# Sheet_1.net
KiCad netlist of a schematic drawn in Altium Designer
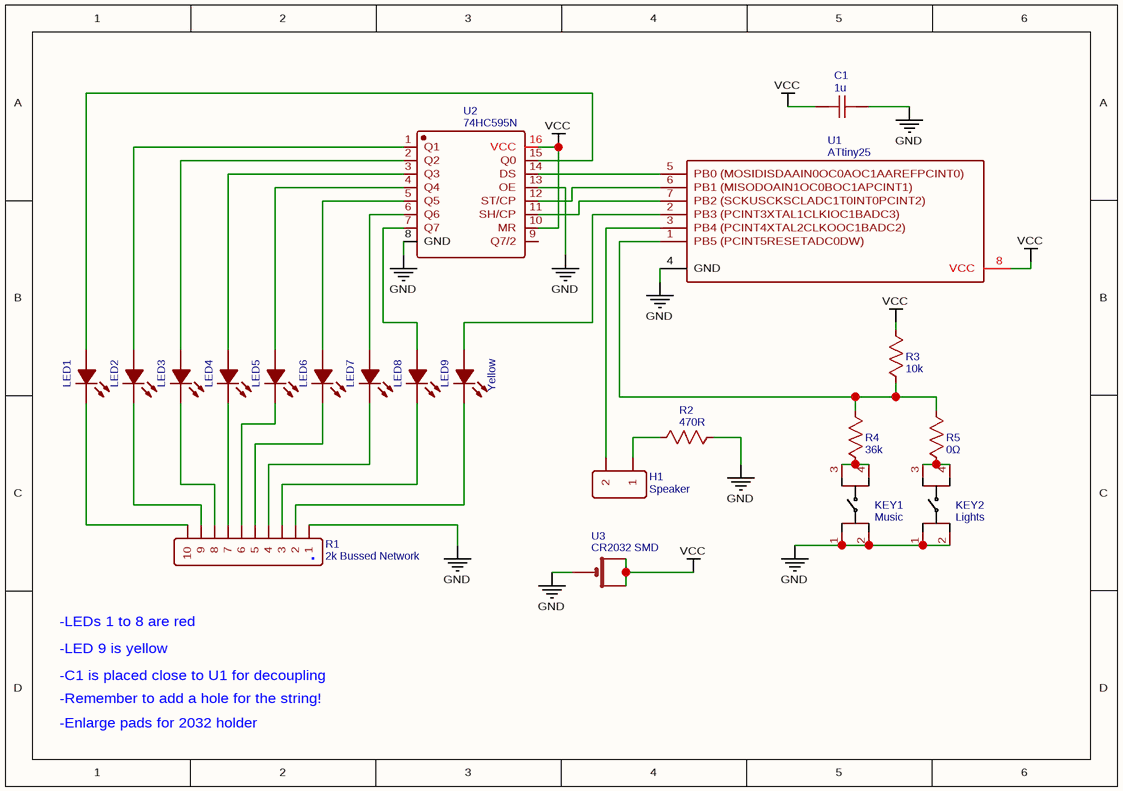
[diagram p0: Sheet_1.schdoc]

(export (version "E")
  (design (tool "Eeschema 10.0.6"))
  (components
    (comp (ref "C1") (value "1u") (libsource (lib "altium-import") (part "root_1_1u_")))
    (comp (ref "H1")
      (value "Speaker")
      (fields (field (name "BOM_MANUFACTURER PART") "826629-2") (field (name "BOM_SUPPLIER PART") "C86471"))
      (libsource (lib "altium-import") (part "root_3_Speaker_"))
    )
    (comp (ref "KEY1")
      (value "Music")
      (fields
        (field (name "BOM_MANUFACTURER PART") "TS-1102-5016")
        (field (name "BOM_SUPPLIER PART") "C111609")
        (field (name "CONTRIBUTOR") "EasyEDA")
      )
      (libsource (lib "altium-import") (part "root_1_Music_"))
    )
    (comp (ref "KEY2")
      (value "Lights")
      (fields
        (field (name "BOM_MANUFACTURER PART") "TS-1102-5016")
        (field (name "BOM_SUPPLIER PART") "C111609")
        (field (name "CONTRIBUTOR") "EasyEDA")
      )
      (libsource (lib "altium-import") (part "root_1_Lights_"))
    )
    (comp (ref "LED1")
      (value "204-10SURD/S530-A3")
      (fields (field (name "BOM_SUPPLIER PART") "C99772"))
      (libsource (lib "altium-import") (part "root_3_204-10SURD/S530-A3_"))
    )
    (comp (ref "LED2")
      (value "204-10SURD/S530-A3")
      (fields (field (name "BOM_SUPPLIER PART") "C99772"))
      (libsource (lib "altium-import") (part "root_3_204-10SURD/S530-A3_"))
    )
    (comp (ref "LED3")
      (value "204-10SURD/S530-A3")
      (fields (field (name "BOM_SUPPLIER PART") "C99772"))
      (libsource (lib "altium-import") (part "root_3_204-10SURD/S530-A3_"))
    )
    (comp (ref "LED4")
      (value "204-10SURD/S530-A3")
      (fields (field (name "BOM_SUPPLIER PART") "C99772"))
      (libsource (lib "altium-import") (part "root_3_204-10SURD/S530-A3_"))
    )
    (comp (ref "LED5")
      (value "204-10SURD/S530-A3")
      (fields (field (name "BOM_SUPPLIER PART") "C99772"))
      (libsource (lib "altium-import") (part "root_3_204-10SURD/S530-A3_"))
    )
    (comp (ref "LED6")
      (value "204-10SURD/S530-A3")
      (fields (field (name "BOM_SUPPLIER PART") "C99772"))
      (libsource (lib "altium-import") (part "root_3_204-10SURD/S530-A3_"))
    )
    (comp (ref "LED7")
      (value "204-10SURD/S530-A3")
      (fields (field (name "BOM_SUPPLIER PART") "C99772"))
      (libsource (lib "altium-import") (part "root_3_204-10SURD/S530-A3_"))
    )
    (comp (ref "LED8")
      (value "204-10SURD/S530-A3")
      (fields (field (name "BOM_SUPPLIER PART") "C99772"))
      (libsource (lib "altium-import") (part "root_3_204-10SURD/S530-A3_"))
    )
    (comp (ref "LED9")
      (value "Yellow")
      (fields
        (field (name "BOM_MANUFACTURER PART") "204-10SURD/S530-A3")
        (field (name "BOM_SUPPLIER PART") "C99772")
      )
      (libsource (lib "altium-import") (part "root_3_Yellow_"))
    )
    (comp (ref "R1")
      (value "2k Bussed Network")
      (fields
        (field (name "BOM_MANUFACTURER PART") "2.54mm 1*10P Straight Female header Gold-plated")
        (field (name "BOM_SUPPLIER PART") "C35445")
      )
      (libsource (lib "altium-import") (part "root_3_2k Bussed Network_"))
    )
    (comp (ref "R2") (value "470R") (libsource (lib "altium-import") (part "root_0_470R_")))
    (comp (ref "R3") (value "10k") (libsource (lib "altium-import") (part "root_1_10k_")))
    (comp (ref "R4") (value "36k") (libsource (lib "altium-import") (part "root_1_36k_")))
    (comp (ref "R5") (value "0Ω") (libsource (lib "altium-import") (part "root_1_0Ω_")))
    (comp (ref "U1") (value "ATtiny25") (libsource (lib "altium-import") (part "root_0_ATtiny25_")))
    (comp (ref "U2") (value "74HC595N") (libsource (lib "altium-import") (part "root_0_74HC595N_")))
    (comp (ref "U3")
      (value "CR2032 SMD")
      (fields (field (name "CONTRIBUTOR") "Adafruit"))
      (libsource (lib "altium-import") (part "root_0_CR2032 SMD_"))
    )
  )
  (nets
    (net (code "1") (name "GND") (class "Default")
      (node (ref "C1") (pin "1") (pinfunction "1_1") (pintype "passive"))
      (node (ref "KEY1") (pin "1") (pinfunction "1_1") (pintype "passive"))
      (node (ref "KEY1") (pin "2") (pinfunction "2_2") (pintype "passive"))
      (node (ref "KEY2") (pin "1") (pinfunction "1_1") (pintype "passive"))
      (node (ref "KEY2") (pin "2") (pinfunction "2_2") (pintype "passive"))
      (node (ref "R1") (pin "1") (pinfunction "1_1") (pintype "passive"))
      (node (ref "R2") (pin "2") (pinfunction "2_2") (pintype "passive"))
      (node (ref "U1") (pin "4") (pinfunction "GND_4") (pintype "passive"))
      (node (ref "U2") (pin "13") (pinfunction "OE_13") (pintype "passive"))
      (node (ref "U2") (pin "8") (pinfunction "GND_8") (pintype "passive"))
      (node (ref "U3") (pin "-") (pinfunction "-_-") (pintype "passive"))
    )
    (net (code "2") (name "Net-(H1-Pad1)") (class "Default")
      (node (ref "H1") (pin "1") (pinfunction "1_1") (pintype "passive"))
      (node (ref "R2") (pin "1") (pinfunction "1_1") (pintype "passive"))
    )
    (net (code "3") (name "Net-(KEY1-Pad3)") (class "Default")
      (node (ref "KEY1") (pin "3") (pinfunction "3_3") (pintype "passive"))
      (node (ref "KEY1") (pin "4") (pinfunction "4_4") (pintype "passive"))
      (node (ref "R4") (pin "1") (pinfunction "1_1") (pintype "passive"))
    )
    (net (code "4") (name "Net-(KEY2-Pad3)") (class "Default")
      (node (ref "KEY2") (pin "3") (pinfunction "3_3") (pintype "passive"))
      (node (ref "KEY2") (pin "4") (pinfunction "4_4") (pintype "passive"))
      (node (ref "R5") (pin "1") (pinfunction "1_1") (pintype "passive"))
    )
    (net (code "5") (name "Net-(LED1-A)") (class "Default")
      (node (ref "LED1") (pin "1") (pinfunction "A_1") (pintype "passive"))
      (node (ref "U2") (pin "15") (pinfunction "Q0_15") (pintype "passive"))
    )
    (net (code "6") (name "Net-(LED1-K)") (class "Default")
      (node (ref "LED1") (pin "2") (pinfunction "K_2") (pintype "passive"))
      (node (ref "R1") (pin "10") (pinfunction "10_10") (pintype "passive"))
    )
    (net (code "7") (name "Net-(LED2-A)") (class "Default")
      (node (ref "LED2") (pin "1") (pinfunction "A_1") (pintype "passive"))
      (node (ref "U2") (pin "1") (pinfunction "Q1_1") (pintype "passive"))
    )
    (net (code "8") (name "Net-(LED2-K)") (class "Default")
      (node (ref "LED2") (pin "2") (pinfunction "K_2") (pintype "passive"))
      (node (ref "R1") (pin "9") (pinfunction "9_9") (pintype "passive"))
    )
    (net (code "9") (name "Net-(LED3-A)") (class "Default")
      (node (ref "LED3") (pin "1") (pinfunction "A_1") (pintype "passive"))
      (node (ref "U2") (pin "2") (pinfunction "Q2_2") (pintype "passive"))
    )
    (net (code "10") (name "Net-(LED3-K)") (class "Default")
      (node (ref "LED3") (pin "2") (pinfunction "K_2") (pintype "passive"))
      (node (ref "R1") (pin "8") (pinfunction "8_8") (pintype "passive"))
    )
    (net (code "11") (name "Net-(LED4-A)") (class "Default")
      (node (ref "LED4") (pin "1") (pinfunction "A_1") (pintype "passive"))
      (node (ref "U2") (pin "3") (pinfunction "Q3_3") (pintype "passive"))
    )
    (net (code "12") (name "Net-(LED4-K)") (class "Default")
      (node (ref "LED4") (pin "2") (pinfunction "K_2") (pintype "passive"))
      (node (ref "R1") (pin "7") (pinfunction "7_7") (pintype "passive"))
    )
    (net (code "13") (name "Net-(LED5-A)") (class "Default")
      (node (ref "LED5") (pin "1") (pinfunction "A_1") (pintype "passive"))
      (node (ref "U2") (pin "4") (pinfunction "Q4_4") (pintype "passive"))
    )
    (net (code "14") (name "Net-(LED5-K)") (class "Default")
      (node (ref "LED5") (pin "2") (pinfunction "K_2") (pintype "passive"))
      (node (ref "R1") (pin "6") (pinfunction "6_6") (pintype "passive"))
    )
    (net (code "15") (name "Net-(LED6-A)") (class "Default")
      (node (ref "LED6") (pin "1") (pinfunction "A_1") (pintype "passive"))
      (node (ref "U2") (pin "5") (pinfunction "Q5_5") (pintype "passive"))
    )
    (net (code "16") (name "Net-(LED6-K)") (class "Default")
      (node (ref "LED6") (pin "2") (pinfunction "K_2") (pintype "passive"))
      (node (ref "R1") (pin "5") (pinfunction "5_5") (pintype "passive"))
    )
    (net (code "17") (name "Net-(LED7-A)") (class "Default")
      (node (ref "LED7") (pin "1") (pinfunction "A_1") (pintype "passive"))
      (node (ref "U2") (pin "6") (pinfunction "Q6_6") (pintype "passive"))
    )
    (net (code "18") (name "Net-(LED7-K)") (class "Default")
      (node (ref "LED7") (pin "2") (pinfunction "K_2") (pintype "passive"))
      (node (ref "R1") (pin "4") (pinfunction "4_4") (pintype "passive"))
    )
    (net (code "19") (name "Net-(LED8-A)") (class "Default")
      (node (ref "LED8") (pin "1") (pinfunction "A_1") (pintype "passive"))
      (node (ref "U2") (pin "7") (pinfunction "Q7_7") (pintype "passive"))
    )
    (net (code "20") (name "Net-(LED8-K)") (class "Default")
      (node (ref "LED8") (pin "2") (pinfunction "K_2") (pintype "passive"))
      (node (ref "R1") (pin "3") (pinfunction "3_3") (pintype "passive"))
    )
    (net (code "21") (name "Net-(LED9-A)") (class "Default")
      (node (ref "LED9") (pin "1") (pinfunction "A_1") (pintype "passive"))
      (node (ref "U1") (pin "2") (pinfunction "PB3_(PCINT3XTAL1CLKIOC1BADC3)_2") (pintype "passive"))
    )
    (net (code "22") (name "Net-(LED9-K)") (class "Default")
      (node (ref "LED9") (pin "2") (pinfunction "K_2") (pintype "passive"))
      (node (ref "R1") (pin "2") (pinfunction "2_2") (pintype "passive"))
    )
    (net (code "23") (name "Net-(U1-PB0_(MOSIDISDAAIN0OC0AOC1AAREFPCINT0))") (class "Default")
      (node (ref "U1") (pin "5") (pinfunction "PB0_(MOSIDISDAAIN0OC0AOC1AAREFPCINT0)_5") (pintype "passive"))
      (node (ref "U2") (pin "14") (pinfunction "DS_14") (pintype "passive"))
    )
    (net (code "24") (name "Net-(U1-PB1_(MISODOAIN1OC0BOC1APCINT1))") (class "Default")
      (node (ref "U1") (pin "6") (pinfunction "PB1_(MISODOAIN1OC0BOC1APCINT1)_6") (pintype "passive"))
      (node (ref "U2") (pin "12") (pinfunction "ST/CP_12") (pintype "passive"))
    )
    (net (code "25") (name "Net-(U1-PB2_(SCKUSCKSCLADC1T0INT0PCINT2))") (class "Default")
      (node (ref "U1") (pin "7") (pinfunction "PB2_(SCKUSCKSCLADC1T0INT0PCINT2)_7") (pintype "passive"))
      (node (ref "U2") (pin "11") (pinfunction "SH/CP_11") (pintype "passive"))
    )
    (net (code "26") (name "Net-(U1-PB4_(PCINT4XTAL2CLKOOC1BADC2))") (class "Default")
      (node (ref "H1") (pin "2") (pinfunction "2_2") (pintype "passive"))
      (node (ref "U1") (pin "3") (pinfunction "PB4_(PCINT4XTAL2CLKOOC1BADC2)_3") (pintype "passive"))
    )
    (net (code "27") (name "Net-(U1-PB5_(PCINT5RESETADC0DW))") (class "Default")
      (node (ref "R3") (pin "1") (pinfunction "1_1") (pintype "passive"))
      (node (ref "R4") (pin "2") (pinfunction "2_2") (pintype "passive"))
      (node (ref "R5") (pin "2") (pinfunction "2_2") (pintype "passive"))
      (node (ref "U1") (pin "1") (pinfunction "PB5_(PCINT5RESETADC0DW)_1") (pintype "passive"))
    )
    (net (code "28") (name "VCC") (class "Default")
      (node (ref "C1") (pin "2") (pinfunction "2_2") (pintype "passive"))
      (node (ref "R3") (pin "2") (pinfunction "2_2") (pintype "passive"))
      (node (ref "U1") (pin "8") (pinfunction "VCC_8") (pintype "passive"))
      (node (ref "U2") (pin "10") (pinfunction "MR_10") (pintype "passive"))
      (node (ref "U2") (pin "16") (pinfunction "VCC_16") (pintype "passive"))
      (node (ref "U3") (pin "+1") (pinfunction "+_+1") (pintype "passive"))
      (node (ref "U3") (pin "+2") (pinfunction "+1_+2") (pintype "passive"))
    )
    (net (code "29") (name "unconnected-(U2-Q7{slash}2-Pad9)") (class "Default")
      (node (ref "U2") (pin "9") (pinfunction "Q7/2_9") (pintype "passive"))
    )
  )
)
